# RFM69W.net
KiCad netlist of a schematic drawn in EAGLE
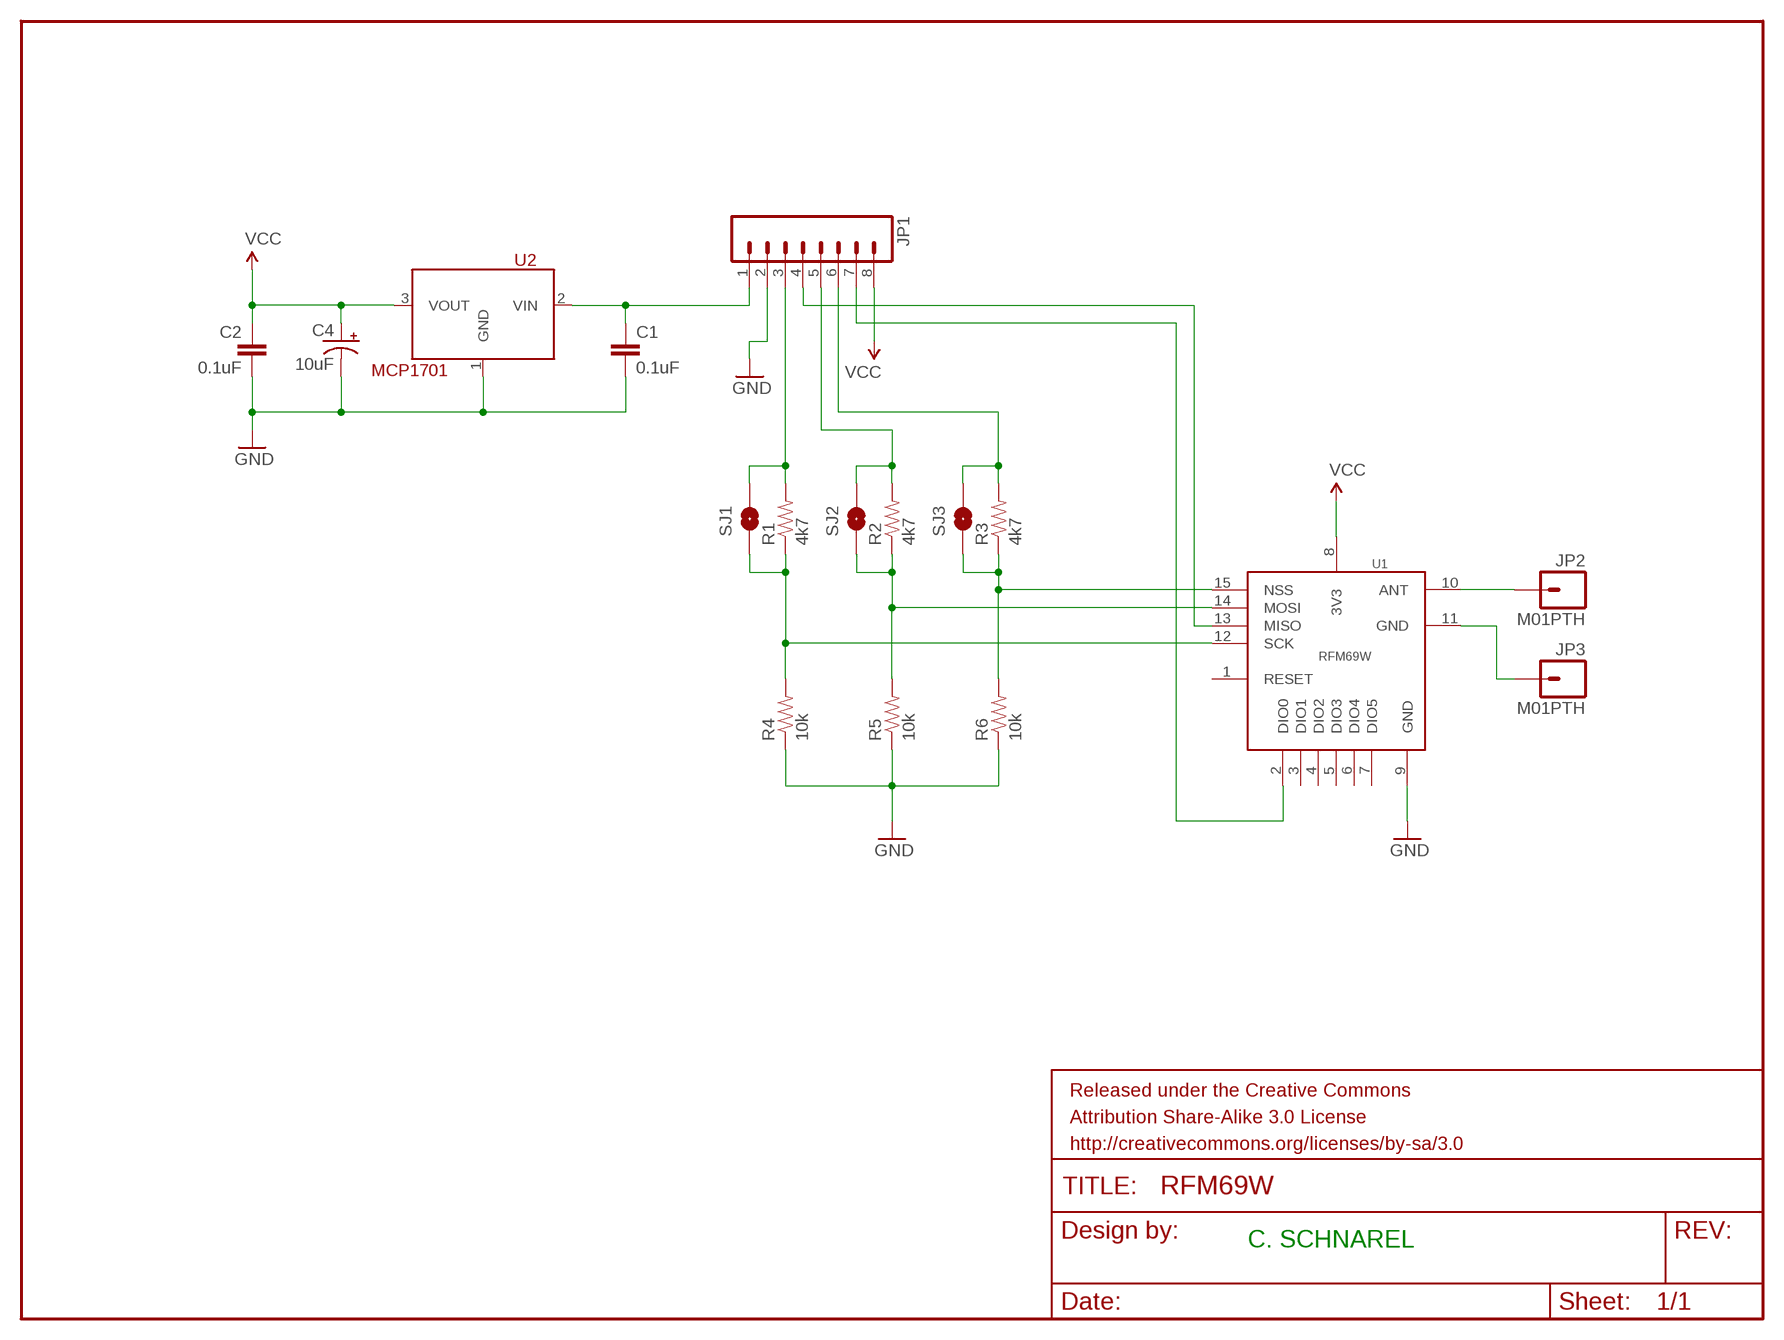
[diagram p0: schematic, sheet 1]

(export (version "E")
  (design (tool "Eeschema 10.0.6"))
  (components
    (comp (ref "C1")
      (value "0.1uF")
      (footprint "eagle-import:0805")
      (libsource (lib "eagle-import") (part "CAP0805"))
    )
    (comp (ref "C2")
      (value "0.1uF")
      (footprint "eagle-import:0805")
      (libsource (lib "eagle-import") (part "CAP0805"))
    )
    (comp (ref "C4")
      (value "10uF")
      (footprint "eagle-import:0805-POL")
      (libsource (lib "eagle-import") (part "CAP_POL0805"))
    )
    (comp (ref "FRAME1")
      (value "FRAME-LETTER")
      (footprint "eagle-import:CREATIVE_COMMONS")
      (libsource (lib "eagle-import") (part "FRAME-LETTER"))
    )
    (comp (ref "JP1")
      (value "M08LONGPADS")
      (footprint "eagle-import:1X08_LONGPADS")
      (libsource (lib "eagle-import") (part "M08LONGPADS"))
    )
    (comp (ref "JP2")
      (value "M01PTH")
      (footprint "eagle-import:1X01")
      (libsource (lib "eagle-import") (part "M01PTH"))
    )
    (comp (ref "JP3")
      (value "M01PTH")
      (footprint "eagle-import:1X01")
      (libsource (lib "eagle-import") (part "M01PTH"))
    )
    (comp (ref "R1")
      (value "4k7")
      (footprint "eagle-import:0805")
      (libsource (lib "eagle-import") (part "RESISTOR0805-RES"))
    )
    (comp (ref "R2")
      (value "4k7")
      (footprint "eagle-import:0805")
      (libsource (lib "eagle-import") (part "RESISTOR0805-RES"))
    )
    (comp (ref "R3")
      (value "4k7")
      (footprint "eagle-import:0805")
      (libsource (lib "eagle-import") (part "RESISTOR0805-RES"))
    )
    (comp (ref "R4")
      (value "10k")
      (footprint "eagle-import:0805")
      (libsource (lib "eagle-import") (part "RESISTOR0805-RES"))
    )
    (comp (ref "R5")
      (value "10k")
      (footprint "eagle-import:0805")
      (libsource (lib "eagle-import") (part "RESISTOR0805-RES"))
    )
    (comp (ref "R6")
      (value "10k")
      (footprint "eagle-import:0805")
      (libsource (lib "eagle-import") (part "RESISTOR0805-RES"))
    )
    (comp (ref "SJ1")
      (value "SOLDERJUMPERNO")
      (footprint "eagle-import:SJ_2S-NO")
      (libsource (lib "eagle-import") (part "SOLDERJUMPERNO"))
    )
    (comp (ref "SJ2")
      (value "SOLDERJUMPERNO")
      (footprint "eagle-import:SJ_2S-NO")
      (libsource (lib "eagle-import") (part "SOLDERJUMPERNO"))
    )
    (comp (ref "SJ3")
      (value "SOLDERJUMPERNO")
      (footprint "eagle-import:SJ_2S-NO")
      (libsource (lib "eagle-import") (part "SOLDERJUMPERNO"))
    )
    (comp (ref "U1")
      (value "RFM69W")
      (footprint "eagle-import:RFM69W")
      (libsource (lib "eagle-import") (part "RFM69W"))
    )
    (comp (ref "U2")
      (value "MCP1701")
      (footprint "eagle-import:SOT-89")
      (libsource (lib "eagle-import") (part "MCP1701"))
    )
  )
  (nets
    (net (code "1") (name "GND") (class "Default")
      (node (ref "C1") (pin "2") (pinfunction "2_2") (pintype "passive"))
      (node (ref "C2") (pin "2") (pinfunction "2_2") (pintype "passive"))
      (node (ref "C4") (pin "2") (pinfunction "-_2") (pintype "passive"))
      (node (ref "JP1") (pin "2") (pinfunction "2_2") (pintype "passive"))
      (node (ref "R4") (pin "1") (pinfunction "1_1") (pintype "passive"))
      (node (ref "R5") (pin "1") (pinfunction "1_1") (pintype "passive"))
      (node (ref "R6") (pin "1") (pinfunction "1_1") (pintype "passive"))
      (node (ref "U1") (pin "9") (pinfunction "GND_9") (pintype "bidirectional"))
      (node (ref "U2") (pin "1") (pinfunction "GND_1") (pintype "bidirectional"))
    )
    (net (code "2") (name "Net-(JP1-Pad3)") (class "Default")
      (node (ref "JP1") (pin "3") (pinfunction "3_3") (pintype "passive"))
      (node (ref "R1") (pin "2") (pinfunction "2_2") (pintype "passive"))
      (node (ref "SJ1") (pin "2") (pinfunction "2_2") (pintype "passive"))
    )
    (net (code "3") (name "Net-(JP1-Pad5)") (class "Default")
      (node (ref "JP1") (pin "5") (pinfunction "5_5") (pintype "passive"))
      (node (ref "R2") (pin "2") (pinfunction "2_2") (pintype "passive"))
      (node (ref "SJ2") (pin "2") (pinfunction "2_2") (pintype "passive"))
    )
    (net (code "4") (name "Net-(JP1-Pad6)") (class "Default")
      (node (ref "JP1") (pin "6") (pinfunction "6_6") (pintype "passive"))
      (node (ref "R3") (pin "2") (pinfunction "2_2") (pintype "passive"))
      (node (ref "SJ3") (pin "2") (pinfunction "2_2") (pintype "passive"))
    )
    (net (code "5") (name "Net-(JP3-Pad1)") (class "Default")
      (node (ref "JP3") (pin "1") (pinfunction "1_1") (pintype "passive"))
      (node (ref "U1") (pin "11") (pinfunction "GND_11") (pintype "bidirectional"))
    )
    (net (code "6") (name "Net-(U1-ANT)") (class "Default")
      (node (ref "JP2") (pin "1") (pinfunction "1_1") (pintype "passive"))
      (node (ref "U1") (pin "10") (pinfunction "ANT_10") (pintype "bidirectional"))
    )
    (net (code "7") (name "Net-(U1-DIO0)") (class "Default")
      (node (ref "JP1") (pin "7") (pinfunction "7_7") (pintype "passive"))
      (node (ref "U1") (pin "2") (pinfunction "DIO0_2") (pintype "bidirectional"))
    )
    (net (code "8") (name "Net-(U1-MISO)") (class "Default")
      (node (ref "JP1") (pin "4") (pinfunction "4_4") (pintype "passive"))
      (node (ref "U1") (pin "13") (pinfunction "MISO_13") (pintype "bidirectional"))
    )
    (net (code "9") (name "Net-(U1-MOSI)") (class "Default")
      (node (ref "R2") (pin "1") (pinfunction "1_1") (pintype "passive"))
      (node (ref "R5") (pin "2") (pinfunction "2_2") (pintype "passive"))
      (node (ref "SJ2") (pin "1") (pinfunction "1_1") (pintype "passive"))
      (node (ref "U1") (pin "14") (pinfunction "MOSI_14") (pintype "bidirectional"))
    )
    (net (code "10") (name "Net-(U1-NSS)") (class "Default")
      (node (ref "R3") (pin "1") (pinfunction "1_1") (pintype "passive"))
      (node (ref "R6") (pin "2") (pinfunction "2_2") (pintype "passive"))
      (node (ref "SJ3") (pin "1") (pinfunction "1_1") (pintype "passive"))
      (node (ref "U1") (pin "15") (pinfunction "NSS_15") (pintype "bidirectional"))
    )
    (net (code "11") (name "Net-(U1-SCK)") (class "Default")
      (node (ref "R1") (pin "1") (pinfunction "1_1") (pintype "passive"))
      (node (ref "R4") (pin "2") (pinfunction "2_2") (pintype "passive"))
      (node (ref "SJ1") (pin "1") (pinfunction "1_1") (pintype "passive"))
      (node (ref "U1") (pin "12") (pinfunction "SCK_12") (pintype "bidirectional"))
    )
    (net (code "12") (name "Net-(U2-VIN)") (class "Default")
      (node (ref "C1") (pin "1") (pinfunction "1_1") (pintype "passive"))
      (node (ref "JP1") (pin "1") (pinfunction "1_1") (pintype "passive"))
      (node (ref "U2") (pin "2") (pinfunction "VIN_2") (pintype "bidirectional"))
    )
    (net (code "13") (name "VCC") (class "Default")
      (node (ref "C2") (pin "1") (pinfunction "1_1") (pintype "passive"))
      (node (ref "C4") (pin "1") (pinfunction "+_1") (pintype "passive"))
      (node (ref "JP1") (pin "8") (pinfunction "8_8") (pintype "passive"))
      (node (ref "U1") (pin "8") (pinfunction "3V3_8") (pintype "bidirectional"))
      (node (ref "U2") (pin "3") (pinfunction "VOUT_3") (pintype "bidirectional"))
    )
    (net (code "14") (name "unconnected-(U1-DIO1-Pad3)") (class "Default")
      (node (ref "U1") (pin "3") (pinfunction "DIO1_3") (pintype "bidirectional"))
    )
    (net (code "15") (name "unconnected-(U1-DIO2-Pad4)") (class "Default")
      (node (ref "U1") (pin "4") (pinfunction "DIO2_4") (pintype "bidirectional"))
    )
    (net (code "16") (name "unconnected-(U1-DIO3-Pad5)") (class "Default")
      (node (ref "U1") (pin "5") (pinfunction "DIO3_5") (pintype "bidirectional"))
    )
    (net (code "17") (name "unconnected-(U1-DIO4-Pad6)") (class "Default")
      (node (ref "U1") (pin "6") (pinfunction "DIO4_6") (pintype "bidirectional"))
    )
    (net (code "18") (name "unconnected-(U1-DIO5-Pad7)") (class "Default")
      (node (ref "U1") (pin "7") (pinfunction "DIO5_7") (pintype "bidirectional"))
    )
    (net (code "19") (name "unconnected-(U1-RESET-Pad1)") (class "Default")
      (node (ref "U1") (pin "1") (pinfunction "RESET_1") (pintype "bidirectional"))
    )
  )
)
